# scematics.net
KiCad netlist of a schematic drawn in EAGLE
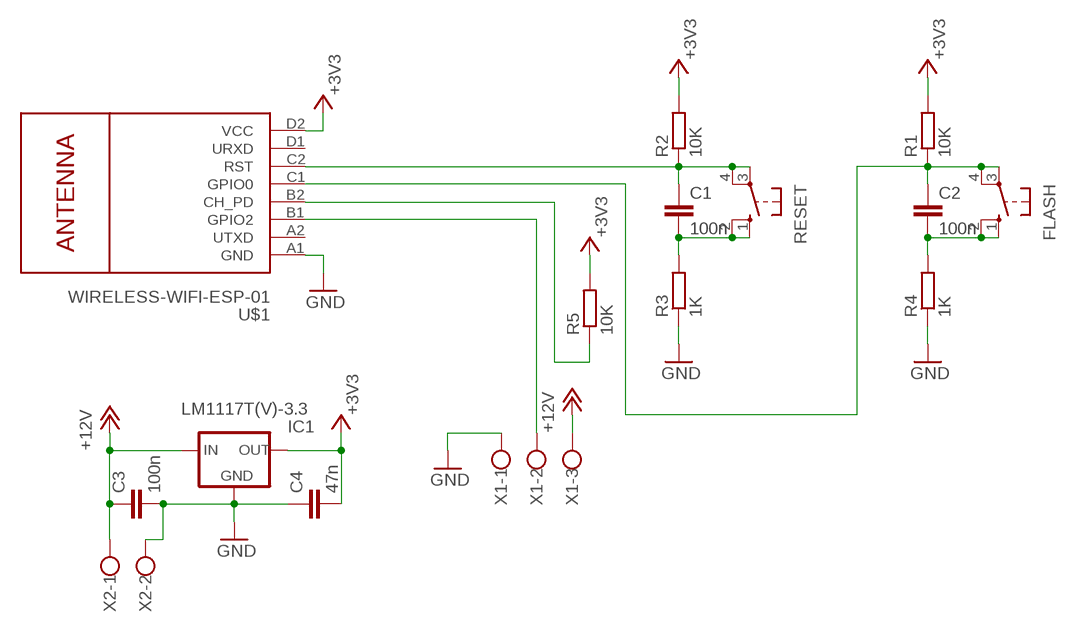
[diagram p0: schematic, sheet 1]

(export (version "E")
  (design (tool "Eeschema 10.0.6"))
  (components
    (comp (ref "C1")
      (value "100n")
      (footprint "eagle-import:C050-030X075")
      (libsource (lib "eagle-import") (part "C-EU050-030X075"))
    )
    (comp (ref "C2")
      (value "100n")
      (footprint "eagle-import:C050-030X075")
      (libsource (lib "eagle-import") (part "C-EU050-030X075"))
    )
    (comp (ref "C3")
      (value "100n")
      (footprint "eagle-import:C050-030X075")
      (libsource (lib "eagle-import") (part "C-EU050-030X075"))
    )
    (comp (ref "C4")
      (value "47n")
      (footprint "eagle-import:C050-030X075")
      (libsource (lib "eagle-import") (part "C-EU050-030X075"))
    )
    (comp (ref "FLASH")
      (value "10-XX")
      (footprint "eagle-import:B3F-10XX")
      (fields (field (name "MPN") "B3F-1000"))
      (libsource (lib "eagle-import") (part "10-XX"))
    )
    (comp (ref "IC1")
      (value "LM1117T(V)-3.3")
      (footprint "eagle-import:TO220V")
      (fields (field (name "MF") "Texas Instruments") (field (name "MPN") "LM1117T-3.3"))
      (libsource (lib "eagle-import") (part "LM1117?-T(V)3.3"))
    )
    (comp (ref "R1")
      (value "10K")
      (footprint "eagle-import:0207_10")
      (libsource (lib "eagle-import") (part "R-EU_0207/10"))
    )
    (comp (ref "R2")
      (value "10K")
      (footprint "eagle-import:0207_10")
      (libsource (lib "eagle-import") (part "R-EU_0207/10"))
    )
    (comp (ref "R3")
      (value "1K")
      (footprint "eagle-import:0207_10")
      (libsource (lib "eagle-import") (part "R-EU_0207/10"))
    )
    (comp (ref "R4")
      (value "1K")
      (footprint "eagle-import:0207_10")
      (libsource (lib "eagle-import") (part "R-EU_0207/10"))
    )
    (comp (ref "R5")
      (value "10K")
      (footprint "eagle-import:0207_10")
      (libsource (lib "eagle-import") (part "R-EU_0207/10"))
    )
    (comp (ref "RESET")
      (value "10-XX")
      (footprint "eagle-import:B3F-10XX")
      (fields (field (name "MPN") "B3F-1000"))
      (libsource (lib "eagle-import") (part "10-XX"))
    )
    (comp (ref "U$1")
      (value "WIRELESS-WIFI-ESP-01")
      (footprint "eagle-import:WIRELESS-WIFI-ESP-01")
      (libsource (lib "eagle-import") (part "WIRELESS-WIFI-ESP-01"))
    )
    (comp (ref "X1")
      (value "W237-103")
      (footprint "eagle-import:W237-103")
      (fields (field (name "MPN") "237-103"))
      (libsource (lib "eagle-import") (part "W237-103"))
    )
    (comp (ref "X2")
      (value "W237-102")
      (footprint "eagle-import:W237-102")
      (fields (field (name "MPN") "237-102"))
      (libsource (lib "eagle-import") (part "W237-102"))
    )
  )
  (nets
    (net (code "1") (name "+3V3") (class "Default")
      (node (ref "C4") (pin "2") (pinfunction "2_2") (pintype "passive"))
      (node (ref "IC1") (pin "2") (pinfunction "OUT_2") (pintype "passive"))
      (node (ref "R1") (pin "2") (pinfunction "2_2") (pintype "passive"))
      (node (ref "R2") (pin "2") (pinfunction "2_2") (pintype "passive"))
      (node (ref "R5") (pin "2") (pinfunction "2_2") (pintype "passive"))
      (node (ref "U$1") (pin "D2") (pinfunction "VCC_D2") (pintype "power_in"))
    )
    (net (code "2") (name "+12V") (class "Default")
      (node (ref "C3") (pin "1") (pinfunction "1_1") (pintype "passive"))
      (node (ref "IC1") (pin "3") (pinfunction "IN_3") (pintype "input"))
      (node (ref "X1") (pin "3") (pinfunction "KL_3") (pintype "passive"))
      (node (ref "X2") (pin "1") (pinfunction "KL_1") (pintype "passive"))
    )
    (net (code "3") (name "GND") (class "Default")
      (node (ref "C3") (pin "2") (pinfunction "2_2") (pintype "passive"))
      (node (ref "C4") (pin "1") (pinfunction "1_1") (pintype "passive"))
      (node (ref "IC1") (pin "1") (pinfunction "GND_1") (pintype "input"))
      (node (ref "R3") (pin "1") (pinfunction "1_1") (pintype "passive"))
      (node (ref "R4") (pin "1") (pinfunction "1_1") (pintype "passive"))
      (node (ref "U$1") (pin "A1") (pinfunction "GND_A1") (pintype "power_in"))
      (node (ref "X1") (pin "1") (pinfunction "KL_1") (pintype "passive"))
      (node (ref "X2") (pin "2") (pinfunction "KL_2") (pintype "passive"))
    )
    (net (code "4") (name "Net-(FLASH-P)") (class "Default")
      (node (ref "C2") (pin "1") (pinfunction "1_1") (pintype "passive"))
      (node (ref "FLASH") (pin "3") (pinfunction "P_3") (pintype "passive"))
      (node (ref "FLASH") (pin "4") (pinfunction "P1_4") (pintype "passive"))
      (node (ref "R1") (pin "1") (pinfunction "1_1") (pintype "passive"))
      (node (ref "U$1") (pin "C1") (pinfunction "GPIO0_C1") (pintype "bidirectional"))
    )
    (net (code "5") (name "Net-(FLASH-S)") (class "Default")
      (node (ref "C2") (pin "2") (pinfunction "2_2") (pintype "passive"))
      (node (ref "FLASH") (pin "1") (pinfunction "S_1") (pintype "passive"))
      (node (ref "FLASH") (pin "2") (pinfunction "S1_2") (pintype "passive"))
      (node (ref "R4") (pin "2") (pinfunction "2_2") (pintype "passive"))
    )
    (net (code "6") (name "Net-(RESET-P)") (class "Default")
      (node (ref "C1") (pin "1") (pinfunction "1_1") (pintype "passive"))
      (node (ref "R2") (pin "1") (pinfunction "1_1") (pintype "passive"))
      (node (ref "RESET") (pin "3") (pinfunction "P_3") (pintype "passive"))
      (node (ref "RESET") (pin "4") (pinfunction "P1_4") (pintype "passive"))
      (node (ref "U$1") (pin "C2") (pinfunction "RST_C2") (pintype "bidirectional"))
    )
    (net (code "7") (name "Net-(RESET-S)") (class "Default")
      (node (ref "C1") (pin "2") (pinfunction "2_2") (pintype "passive"))
      (node (ref "R3") (pin "2") (pinfunction "2_2") (pintype "passive"))
      (node (ref "RESET") (pin "1") (pinfunction "S_1") (pintype "passive"))
      (node (ref "RESET") (pin "2") (pinfunction "S1_2") (pintype "passive"))
    )
    (net (code "8") (name "Net-(U$1-CH_PD)") (class "Default")
      (node (ref "R5") (pin "1") (pinfunction "1_1") (pintype "passive"))
      (node (ref "U$1") (pin "B2") (pinfunction "CH_PD_B2") (pintype "bidirectional"))
    )
    (net (code "9") (name "Net-(U$1-GPIO2)") (class "Default")
      (node (ref "U$1") (pin "B1") (pinfunction "GPIO2_B1") (pintype "bidirectional"))
      (node (ref "X1") (pin "2") (pinfunction "KL_2") (pintype "passive"))
    )
    (net (code "10") (name "unconnected-(U$1-URXD-PadD1)") (class "Default")
      (node (ref "U$1") (pin "D1") (pinfunction "URXD_D1") (pintype "bidirectional"))
    )
    (net (code "11") (name "unconnected-(U$1-UTXD-PadA2)") (class "Default")
      (node (ref "U$1") (pin "A2") (pinfunction "UTXD_A2") (pintype "bidirectional"))
    )
  )
)
